# DACN_shematic.net
KiCad netlist of a schematic drawn in Altium Designer
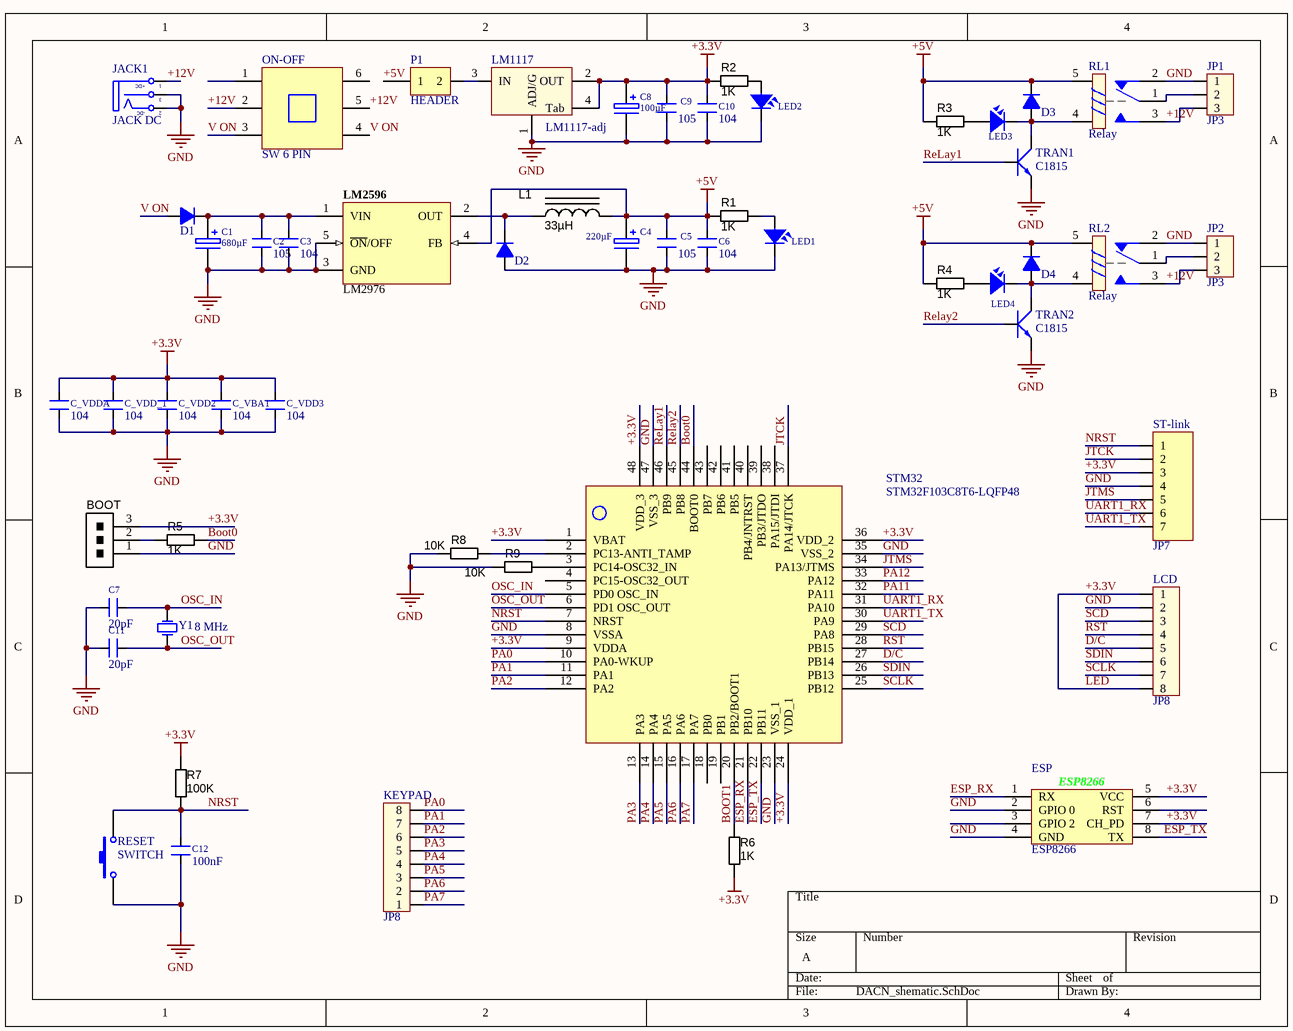
[diagram p0: DACN_shematic.SchDoc]

(export (version "E")
  (design (tool "Eeschema 10.0.6"))
  (components
    (comp (ref "BOOT")
      (value "CONN_HEADER_1x3P_0.100in")
      (footprint "1x3POS_HEADER")
      (description "Pin Header, THT, Single-row, 2.54mm pitch")
      (libsource (lib "My library altium") (part "CONN_HEADER_1x3P_0.100in"))
    )
    (comp (ref "C1")
      (value "10µF")
      (footprint "CAP_ELEC_5x5.7")
      (fields (field (name "ALTIUM_UNNAMED_1") "680µF"))
      (libsource (lib "My library altium") (part "CAP Aluminum"))
    )
    (comp (ref "C2")
      (value "105")
      (footprint "SM-CAP-0805")
      (fields (field (name "DESIGNED BY") "VanDungEvn"))
      (libsource (lib "My library altium") (part "CAP SMD"))
    )
    (comp (ref "C3")
      (value "104")
      (footprint "SM-CAP-0805")
      (fields (field (name "DESIGNED BY") "VanDungEvn"))
      (libsource (lib "My library altium") (part "CAP SMD"))
    )
    (comp (ref "C4")
      (value "10µF")
      (footprint "CAP_ELEC_5x5.7")
      (fields (field (name "ALTIUM_UNNAMED_1") "220µF"))
      (libsource (lib "My library altium") (part "CAP Aluminum"))
    )
    (comp (ref "C5")
      (value "105")
      (footprint "SM-CAP-0805")
      (fields (field (name "DESIGNED BY") "VanDungEvn"))
      (libsource (lib "My library altium") (part "CAP SMD"))
    )
    (comp (ref "C6")
      (value "104")
      (footprint "SM-CAP-0805")
      (fields (field (name "DESIGNED BY") "VanDungEvn"))
      (libsource (lib "My library altium") (part "CAP SMD"))
    )
    (comp (ref "C7")
      (value "20pF")
      (footprint "SM-CAP-0805")
      (fields (field (name "DESIGNED BY") "VanDungEvn"))
      (libsource (lib "My library altium") (part "CAP SMD"))
    )
    (comp (ref "C8")
      (value "10µF")
      (footprint "CAP_ELEC_5x5.7")
      (fields (field (name "ALTIUM_UNNAMED_1") "100µF"))
      (libsource (lib "My library altium") (part "CAP Aluminum"))
    )
    (comp (ref "C9")
      (value "105")
      (footprint "SM-CAP-0805")
      (fields (field (name "DESIGNED BY") "VanDungEvn"))
      (libsource (lib "My library altium") (part "CAP SMD"))
    )
    (comp (ref "C10")
      (value "104")
      (footprint "SM-CAP-0805")
      (fields (field (name "DESIGNED BY") "VanDungEvn"))
      (libsource (lib "My library altium") (part "CAP SMD"))
    )
    (comp (ref "C11")
      (value "20pF")
      (footprint "SM-CAP-0805")
      (fields (field (name "DESIGNED BY") "VanDungEvn"))
      (libsource (lib "My library altium") (part "CAP SMD"))
    )
    (comp (ref "C12")
      (value "100nF")
      (footprint "SM-CAP-0805")
      (fields (field (name "DESIGNED BY") "VanDungEvn"))
      (libsource (lib "My library altium") (part "CAP SMD"))
    )
    (comp (ref "C_VBAT")
      (value "104")
      (footprint "SM-CAP-0805")
      (fields (field (name "DESIGNED BY") "VanDungEvn"))
      (libsource (lib "My library altium") (part "CAP SMD"))
    )
    (comp (ref "C_VDD2")
      (value "104")
      (footprint "SM-CAP-0805")
      (fields (field (name "DESIGNED BY") "VanDungEvn"))
      (libsource (lib "My library altium") (part "CAP SMD"))
    )
    (comp (ref "C_VDD3")
      (value "104")
      (footprint "SM-CAP-0805")
      (fields (field (name "DESIGNED BY") "VanDungEvn"))
      (libsource (lib "My library altium") (part "CAP SMD"))
    )
    (comp (ref "C_VDDA")
      (value "104")
      (footprint "SM-CAP-0805")
      (fields (field (name "DESIGNED BY") "VanDungEvn"))
      (libsource (lib "My library altium") (part "CAP SMD"))
    )
    (comp (ref "C_VDD_1")
      (value "104")
      (footprint "SM-CAP-0805")
      (fields (field (name "DESIGNED BY") "VanDungEvn"))
      (libsource (lib "My library altium") (part "CAP SMD"))
    )
    (comp (ref "D1")
      (value "Diode  1N4007")
      (footprint "DO-214AC")
      (description "Diode 1A")
      (libsource (lib "My library altium") (part "Diode  1N4007"))
    )
    (comp (ref "D2")
      (value "Diode  1N4007")
      (footprint "DO-214AC")
      (description "Diode 1A")
      (libsource (lib "My library altium") (part "Diode  1N4007"))
    )
    (comp (ref "D3")
      (value "Diode  1N4007")
      (footprint "DO-214AC")
      (description "Diode 1A")
      (libsource (lib "My library altium") (part "Diode  1N4007"))
    )
    (comp (ref "D4")
      (value "Diode  1N4007")
      (footprint "DO-214AC")
      (description "Diode 1A")
      (libsource (lib "My library altium") (part "Diode  1N4007"))
    )
    (comp (ref "ESP")
      (value "ESP8266")
      (footprint "ESP2866")
      (libsource (lib "My library altium") (part "ESP8266"))
    )
    (comp (ref "JACK1")
      (value "JACK DC")
      (footprint "JACK DC")
      (libsource (lib "ThinhNguyenLib") (part "JACK DC"))
    )
    (comp (ref "JP1")
      (value "JP3")
      (footprint "CON3")
      (description "Connector 3")
      (libsource (lib "My library altium") (part "Con3"))
    )
    (comp (ref "JP2")
      (value "JP3")
      (footprint "CON3")
      (description "Connector 3")
      (libsource (lib "My library altium") (part "Con3"))
    )
    (comp (ref "KEYPAD")
      (value "JP8")
      (footprint "jam8")
      (description "jam 8")
      (libsource (lib "") (part "jam 8_1"))
    )
    (comp (ref "L1")
      (value "33µH")
      (footprint "IND_WW_DR73")
      (description "Inductor Power 10µH 2.1A 7.6x7.6mm SMD")
      (fields (field (name "TOLERANCE") "±20%"))
      (libsource (lib "My library altium") (part "INDC_10u_DR73-100-R"))
    )
    (comp (ref "LCD")
      (value "JP8")
      (footprint "jam8")
      (description "jam 8")
      (libsource (lib "My library altium") (part "jam 8"))
    )
    (comp (ref "LED1")
      (value "LED SMD")
      (footprint "SM-LED-0805-Blue")
      (libsource (lib "My library altium") (part "LED SMD 0805"))
    )
    (comp (ref "LED2")
      (value "LED SMD")
      (footprint "SM-LED-0805-Blue")
      (libsource (lib "My library altium") (part "LED SMD 0805"))
    )
    (comp (ref "LED3")
      (value "LED SMD")
      (footprint "SM-LED-0805-Blue")
      (libsource (lib "My library altium") (part "LED SMD 0805"))
    )
    (comp (ref "LED4")
      (value "LED SMD")
      (footprint "SM-LED-0805-Blue")
      (libsource (lib "My library altium") (part "LED SMD 0805"))
    )
    (comp (ref "LM1117")
      (value "LM1117-adj")
      (footprint "SOT223-4N")
      (description "3v3")
      (libsource (lib "My library altium") (part "LM1117-adj"))
    )
    (comp (ref "LM2596") (value "LM2976") (footprint "TO263") (libsource (lib "LIBRARY") (part "LM2596")))
    (comp (ref "ON-OFF")
      (value "SW 6 PIN")
      (footprint "SW6")
      (libsource (lib "ThinhNguyenLib") (part "SW 6 PIN"))
    )
    (comp (ref "P1")
      (value "HEADER")
      (footprint "JUMPER PITCH 2 PIN")
      (libsource (lib "ThinhNguyenLib") (part "HEADER CONNECT"))
    )
    (comp (ref "R1")
      (value "1K")
      (footprint "RESC2012N_ZERO")
      (description "Resistor SMD chip 0.0 Ohm 0.125W 0805")
      (fields (field (name "Comment") "Jumper"))
      (libsource (lib "") (part "RES_0805_1"))
    )
    (comp (ref "R2")
      (value "1K")
      (footprint "RESC2012N_ZERO")
      (description "Resistor SMD chip 0.0 Ohm 0.125W 0805")
      (fields (field (name "Comment") "Jumper"))
      (libsource (lib "") (part "RES_0805_1"))
    )
    (comp (ref "R3")
      (value "1K")
      (footprint "RESC2012N_ZERO")
      (description "Resistor SMD chip 0.0 Ohm 0.125W 0805")
      (fields (field (name "Comment") "Jumper"))
      (libsource (lib "") (part "RES_0805_1"))
    )
    (comp (ref "R4")
      (value "1K")
      (footprint "RESC2012N_ZERO")
      (description "Resistor SMD chip 0.0 Ohm 0.125W 0805")
      (fields (field (name "Comment") "Jumper"))
      (libsource (lib "") (part "RES_0805_1"))
    )
    (comp (ref "R5")
      (value "1K")
      (footprint "RESC2012N_ZERO")
      (description "Resistor SMD chip 0.0 Ohm 0.125W 0805")
      (fields (field (name "Comment") "Jumper"))
      (libsource (lib "") (part "RES_0805_1"))
    )
    (comp (ref "R6")
      (value "1K")
      (footprint "RESC2012N_ZERO")
      (description "Resistor SMD chip 0.0 Ohm 0.125W 0805")
      (fields (field (name "Comment") "Jumper"))
      (libsource (lib "") (part "RES_0805_2"))
    )
    (comp (ref "R7")
      (value "100K")
      (footprint "RESC2012N_ZERO")
      (description "Resistor SMD chip 0.0 Ohm 0.125W 0805")
      (fields (field (name "Comment") "Jumper"))
      (libsource (lib "") (part "RES_0805_2"))
    )
    (comp (ref "R8")
      (value "10K")
      (footprint "RESC2012N_ZERO")
      (description "Resistor SMD chip 0.0 Ohm 0.125W 0805")
      (fields (field (name "Comment") "Jumper"))
      (libsource (lib "My library altium") (part "RES_0805"))
    )
    (comp (ref "R9")
      (value "10K")
      (footprint "RESC2012N_ZERO")
      (description "Resistor SMD chip 0.0 Ohm 0.125W 0805")
      (fields (field (name "Comment") "Jumper"))
      (libsource (lib "My library altium") (part "RES_0805"))
    )
    (comp (ref "RESET")
      (value "SWITCH")
      (footprint "SW 4PIN")
      (fields (field (name "PUBLISHER") "Altium Limited"))
      (libsource (lib "ThinhNguyenLib") (part "SWITCH"))
    )
    (comp (ref "RL1")
      (value "Relay")
      (footprint "RL_SPDT_10A")
      (description "Relay SPDT 5 Pin")
      (libsource (lib "My library altium") (part "Relay SRD"))
    )
    (comp (ref "RL2")
      (value "Relay")
      (footprint "RL_SPDT_10A")
      (description "Relay SPDT 5 Pin")
      (libsource (lib "My library altium") (part "Relay SRD"))
    )
    (comp (ref "ST-link")
      (value "JP7")
      (footprint "JP7-D1T")
      (description "WR-PHD 2.54 mm Angled Socket Header")
      (fields
        (field (name "MANUFACTURER") "Würth Elektronik eiSos GmbH")
        (field (name "PARTNO") "613007143121")
        (field (name "CREATED BY") "Karrer Zheng")
      )
      (libsource (lib "LIBRARY") (part "JP7"))
    )
    (comp (ref "STM32")
      (value "STM32F103C8T6-LQFP48")
      (footprint "LQFP 48 PIN")
      (fields (field (name "PUBLISHER") "Altium Limited"))
      (libsource (lib "ThinhNguyenLib") (part "STM32F103C8T6-LQFP48"))
    )
    (comp (ref "TRAN1")
      (value "C1815")
      (footprint "C1815")
      (description "NPN 600mW, ECB")
      (libsource (lib "My library altium") (part "C1815"))
    )
    (comp (ref "TRAN2")
      (value "C1815")
      (footprint "C1815")
      (description "NPN 600mW, ECB")
      (libsource (lib "My library altium") (part "C1815"))
    )
    (comp (ref "Y1")
      (value "8 MHz")
      (footprint "CRYSTAL DIP")
      (fields (field (name "PUBLISHER") "Altium Limited"))
      (libsource (lib "ThinhNguyenLib") (part "Crystal"))
    )
  )
  (nets
    (net (code "1") (name "+3.3V") (class "Default")
      (node (ref "BOOT") (pin "3") (pinfunction "3_3") (pintype "passive"))
      (node (ref "C10") (pin "2") (pinfunction "2_2") (pintype "passive"))
      (node (ref "C8") (pin "1") (pintype "passive"))
      (node (ref "C9") (pin "2") (pinfunction "2_2") (pintype "passive"))
      (node (ref "C_VBAT") (pin "2") (pinfunction "2_2") (pintype "passive"))
      (node (ref "C_VDD2") (pin "2") (pinfunction "2_2") (pintype "passive"))
      (node (ref "C_VDD3") (pin "2") (pinfunction "2_2") (pintype "passive"))
      (node (ref "C_VDDA") (pin "2") (pinfunction "2_2") (pintype "passive"))
      (node (ref "C_VDD_1") (pin "2") (pinfunction "2_2") (pintype "passive"))
      (node (ref "ESP") (pin "5") (pinfunction "VCC_5") (pintype "passive"))
      (node (ref "ESP") (pin "7") (pinfunction "CH_PD_7") (pintype "passive"))
      (node (ref "LCD") (pin "1") (pinfunction "1_1") (pintype "passive"))
      (node (ref "LCD") (pin "8") (pinfunction "8_8") (pintype "passive"))
      (node (ref "LM1117") (pin "2") (pinfunction "OUT_2") (pintype "passive"))
      (node (ref "LM1117") (pin "4") (pinfunction "Tab_4") (pintype "passive"))
      (node (ref "R2") (pin "1") (pinfunction "1_1") (pintype "passive"))
      (node (ref "R6") (pin "1") (pinfunction "1_1") (pintype "passive"))
      (node (ref "R7") (pin "2") (pinfunction "2_2") (pintype "passive"))
      (node (ref "ST-link") (pin "3") (pinfunction "3_3") (pintype "passive"))
      (node (ref "STM32") (pin "1") (pinfunction "VBAT_1") (pintype "passive"))
      (node (ref "STM32") (pin "24") (pinfunction "VDD_1_24") (pintype "passive"))
      (node (ref "STM32") (pin "36") (pinfunction "VDD_2_36") (pintype "passive"))
      (node (ref "STM32") (pin "48") (pinfunction "VDD_3_48") (pintype "passive"))
      (node (ref "STM32") (pin "9") (pinfunction "VDDA_9") (pintype "passive"))
    )
    (net (code "2") (name "+5V") (class "Default")
      (node (ref "C4") (pin "1") (pintype "passive"))
      (node (ref "C5") (pin "2") (pinfunction "2_2") (pintype "passive"))
      (node (ref "C6") (pin "2") (pinfunction "2_2") (pintype "passive"))
      (node (ref "D3") (pin "K") (pinfunction "K_K") (pintype "passive"))
      (node (ref "D4") (pin "K") (pinfunction "K_K") (pintype "passive"))
      (node (ref "L1") (pin "2") (pinfunction "2_2") (pintype "passive"))
      (node (ref "LM2596") (pin "4") (pinfunction "FB_4") (pintype "input"))
      (node (ref "P1") (pin "1") (pinfunction "1_1") (pintype "passive"))
      (node (ref "R1") (pin "1") (pinfunction "1_1") (pintype "passive"))
      (node (ref "R3") (pin "1") (pinfunction "1_1") (pintype "passive"))
      (node (ref "R4") (pin "1") (pinfunction "1_1") (pintype "passive"))
      (node (ref "RL1") (pin "5") (pinfunction "5_5") (pintype "passive"))
      (node (ref "RL2") (pin "5") (pinfunction "5_5") (pintype "passive"))
    )
    (net (code "3") (name "/+12V") (class "Default")
      (node (ref "JACK1") (pin "1") (pinfunction "T_1") (pintype "passive"))
      (node (ref "JP1") (pin "3") (pinfunction "3_3") (pintype "passive"))
      (node (ref "JP2") (pin "3") (pinfunction "3_3") (pintype "passive"))
      (node (ref "ON-OFF") (pin "2") (pinfunction "2_2") (pintype "passive"))
      (node (ref "ON-OFF") (pin "5") (pinfunction "5_5") (pintype "passive"))
      (node (ref "RL1") (pin "3") (pinfunction "3_3") (pintype "passive"))
      (node (ref "RL2") (pin "3") (pinfunction "3_3") (pintype "passive"))
    )
    (net (code "4") (name "/BOOT1") (class "Default")
      (node (ref "R6") (pin "2") (pinfunction "2_2") (pintype "passive"))
      (node (ref "STM32") (pin "20") (pinfunction "PB2/BOOT1_20") (pintype "passive"))
    )
    (net (code "5") (name "/Boot0") (class "Default")
      (node (ref "R5") (pin "2") (pinfunction "2_2") (pintype "passive"))
      (node (ref "STM32") (pin "44") (pinfunction "BOOT0_44") (pintype "passive"))
    )
    (net (code "6") (name "/D{slash}C") (class "Default")
      (node (ref "LCD") (pin "5") (pinfunction "5_5") (pintype "passive"))
      (node (ref "STM32") (pin "27") (pinfunction "PB14_27") (pintype "passive"))
    )
    (net (code "7") (name "/ESP_RX") (class "Default")
      (node (ref "ESP") (pin "1") (pinfunction "RX_1") (pintype "passive"))
      (node (ref "STM32") (pin "21") (pinfunction "PB10_21") (pintype "passive"))
    )
    (net (code "8") (name "/ESP_TX") (class "Default")
      (node (ref "ESP") (pin "8") (pinfunction "TX_8") (pintype "passive"))
      (node (ref "STM32") (pin "22") (pinfunction "PB11_22") (pintype "passive"))
    )
    (net (code "9") (name "/JTCK") (class "Default")
      (node (ref "ST-link") (pin "2") (pinfunction "2_2") (pintype "passive"))
      (node (ref "STM32") (pin "37") (pinfunction "PA14/JTCK_37") (pintype "passive"))
    )
    (net (code "10") (name "/JTMS") (class "Default")
      (node (ref "ST-link") (pin "5") (pinfunction "5_5") (pintype "passive"))
      (node (ref "STM32") (pin "34") (pinfunction "PA13/JTMS_34") (pintype "passive"))
    )
    (net (code "11") (name "/NRST") (class "Default")
      (node (ref "C12") (pin "1") (pinfunction "1_1") (pintype "passive"))
      (node (ref "R7") (pin "1") (pinfunction "1_1") (pintype "passive"))
      (node (ref "RESET") (pin "2") (pinfunction "2_2") (pintype "passive"))
      (node (ref "ST-link") (pin "1") (pinfunction "1_1") (pintype "passive"))
      (node (ref "STM32") (pin "7") (pinfunction "NRST_7") (pintype "passive"))
    )
    (net (code "12") (name "/OSC_IN") (class "Default")
      (node (ref "C7") (pin "1") (pinfunction "1_1") (pintype "passive"))
      (node (ref "STM32") (pin "5") (pinfunction "PD0_OSC_IN_5") (pintype "passive"))
      (node (ref "Y1") (pin "2") (pinfunction "OSC2_2") (pintype "passive"))
    )
    (net (code "13") (name "/OSC_OUT") (class "Default")
      (node (ref "C11") (pin "1") (pinfunction "1_1") (pintype "passive"))
      (node (ref "STM32") (pin "6") (pinfunction "PD1_OSC_OUT_6") (pintype "passive"))
      (node (ref "Y1") (pin "1") (pinfunction "OSC1_1") (pintype "passive"))
    )
    (net (code "14") (name "/PA0") (class "Default")
      (node (ref "KEYPAD") (pin "8") (pinfunction "8_8") (pintype "passive"))
      (node (ref "STM32") (pin "10") (pinfunction "PA0-WKUP_10") (pintype "passive"))
    )
    (net (code "15") (name "/PA1") (class "Default")
      (node (ref "KEYPAD") (pin "7") (pinfunction "7_7") (pintype "passive"))
      (node (ref "STM32") (pin "11") (pinfunction "PA1_11") (pintype "passive"))
    )
    (net (code "16") (name "/PA2") (class "Default")
      (node (ref "KEYPAD") (pin "6") (pinfunction "6_6") (pintype "passive"))
      (node (ref "STM32") (pin "12") (pinfunction "PA2_12") (pintype "passive"))
    )
    (net (code "17") (name "/PA3") (class "Default")
      (node (ref "KEYPAD") (pin "5") (pinfunction "5_5") (pintype "passive"))
      (node (ref "STM32") (pin "13") (pinfunction "PA3_13") (pintype "passive"))
    )
    (net (code "18") (name "/PA4") (class "Default")
      (node (ref "KEYPAD") (pin "4") (pinfunction "4_4") (pintype "passive"))
      (node (ref "STM32") (pin "14") (pinfunction "PA4_14") (pintype "passive"))
    )
    (net (code "19") (name "/PA5") (class "Default")
      (node (ref "KEYPAD") (pin "3") (pinfunction "3_3") (pintype "passive"))
      (node (ref "STM32") (pin "15") (pinfunction "PA5_15") (pintype "passive"))
    )
    (net (code "20") (name "/PA6") (class "Default")
      (node (ref "KEYPAD") (pin "2") (pinfunction "2_2") (pintype "passive"))
      (node (ref "STM32") (pin "16") (pinfunction "PA6_16") (pintype "passive"))
    )
    (net (code "21") (name "/PA7") (class "Default")
      (node (ref "KEYPAD") (pin "1") (pinfunction "1_1") (pintype "passive"))
      (node (ref "STM32") (pin "17") (pinfunction "PA7_17") (pintype "passive"))
    )
    (net (code "22") (name "/PA11") (class "Default")
      (node (ref "STM32") (pin "32") (pinfunction "PA11_32") (pintype "passive"))
    )
    (net (code "23") (name "/PA12") (class "Default")
      (node (ref "STM32") (pin "33") (pinfunction "PA12_33") (pintype "passive"))
    )
    (net (code "24") (name "/RST") (class "Default")
      (node (ref "LCD") (pin "4") (pinfunction "4_4") (pintype "passive"))
      (node (ref "STM32") (pin "28") (pinfunction "PB15_28") (pintype "passive"))
    )
    (net (code "25") (name "/ReLay1") (class "Default")
      (node (ref "STM32") (pin "46") (pinfunction "PB9_46") (pintype "passive"))
      (node (ref "TRAN1") (pin "1") (pinfunction "B_1") (pintype "passive"))
    )
    (net (code "26") (name "/Relay2") (class "Default")
      (node (ref "STM32") (pin "45") (pinfunction "PB8_45") (pintype "passive"))
      (node (ref "TRAN2") (pin "1") (pinfunction "B_1") (pintype "passive"))
    )
    (net (code "27") (name "/SCD") (class "Default")
      (node (ref "LCD") (pin "3") (pinfunction "3_3") (pintype "passive"))
      (node (ref "STM32") (pin "29") (pinfunction "PA8_29") (pintype "passive"))
    )
    (net (code "28") (name "/SCLK") (class "Default")
      (node (ref "LCD") (pin "7") (pinfunction "7_7") (pintype "passive"))
      (node (ref "STM32") (pin "25") (pinfunction "PB12_25") (pintype "passive"))
    )
    (net (code "29") (name "/SDIN") (class "Default")
      (node (ref "LCD") (pin "6") (pinfunction "6_6") (pintype "passive"))
      (node (ref "STM32") (pin "26") (pinfunction "PB13_26") (pintype "passive"))
    )
    (net (code "30") (name "/UART1_RX") (class "Default")
      (node (ref "ST-link") (pin "6") (pinfunction "6_6") (pintype "passive"))
      (node (ref "STM32") (pin "31") (pinfunction "PA10_31") (pintype "passive"))
    )
    (net (code "31") (name "/UART1_TX") (class "Default")
      (node (ref "ST-link") (pin "7") (pinfunction "7_7") (pintype "passive"))
      (node (ref "STM32") (pin "30") (pinfunction "PA9_30") (pintype "passive"))
    )
    (net (code "32") (name "/V ON") (class "Default")
      (node (ref "D1") (pin "A") (pinfunction "A_A") (pintype "passive"))
      (node (ref "ON-OFF") (pin "3") (pinfunction "3_3") (pintype "passive"))
      (node (ref "ON-OFF") (pin "4") (pinfunction "4_4") (pintype "passive"))
    )
    (net (code "33") (name "GND") (class "Default")
      (node (ref "BOOT") (pin "1") (pinfunction "1_1") (pintype "passive"))
      (node (ref "C1") (pin "2") (pintype "passive"))
      (node (ref "C10") (pin "1") (pinfunction "1_1") (pintype "passive"))
      (node (ref "C11") (pin "2") (pinfunction "2_2") (pintype "passive"))
      (node (ref "C12") (pin "2") (pinfunction "2_2") (pintype "passive"))
      (node (ref "C2") (pin "1") (pinfunction "1_1") (pintype "passive"))
      (node (ref "C3") (pin "1") (pinfunction "1_1") (pintype "passive"))
      (node (ref "C4") (pin "2") (pintype "passive"))
      (node (ref "C5") (pin "1") (pinfunction "1_1") (pintype "passive"))
      (node (ref "C6") (pin "1") (pinfunction "1_1") (pintype "passive"))
      (node (ref "C7") (pin "2") (pinfunction "2_2") (pintype "passive"))
      (node (ref "C8") (pin "2") (pintype "passive"))
      (node (ref "C9") (pin "1") (pinfunction "1_1") (pintype "passive"))
      (node (ref "C_VBAT") (pin "1") (pinfunction "1_1") (pintype "passive"))
      (node (ref "C_VDD2") (pin "1") (pinfunction "1_1") (pintype "passive"))
      (node (ref "C_VDD3") (pin "1") (pinfunction "1_1") (pintype "passive"))
      (node (ref "C_VDDA") (pin "1") (pinfunction "1_1") (pintype "passive"))
      (node (ref "C_VDD_1") (pin "1") (pinfunction "1_1") (pintype "passive"))
      (node (ref "D2") (pin "A") (pinfunction "A_A") (pintype "passive"))
      (node (ref "ESP") (pin "2") (pinfunction "GPIO_0_2") (pintype "passive"))
      (node (ref "ESP") (pin "4") (pinfunction "GND_4") (pintype "passive"))
      (node (ref "JACK1") (pin "2") (pinfunction "TN_2") (pintype "passive"))
      (node (ref "JACK1") (pin "3") (pinfunction "S_3") (pintype "power_in"))
      (node (ref "JP1") (pin "1") (pinfunction "1_1") (pintype "passive"))
      (node (ref "JP2") (pin "1") (pinfunction "1_1") (pintype "passive"))
      (node (ref "LCD") (pin "2") (pinfunction "2_2") (pintype "passive"))
      (node (ref "LED1") (pin "2") (pinfunction "2_2") (pintype "passive"))
      (node (ref "LED2") (pin "2") (pinfunction "2_2") (pintype "passive"))
      (node (ref "LM1117") (pin "1") (pinfunction "ADJ/G_1") (pintype "passive"))
      (node (ref "LM2596") (pin "3") (pinfunction "GND_3") (pintype "power_in"))
      (node (ref "LM2596") (pin "5") (pinfunction "~{ON}/OFF_5") (pintype "input"))
      (node (ref "R8") (pin "2") (pinfunction "2_2") (pintype "passive"))
      (node (ref "R9") (pin "2") (pinfunction "2_2") (pintype "passive"))
      (node (ref "RESET") (pin "1") (pinfunction "1_1") (pintype "passive"))
      (node (ref "RL1") (pin "2") (pinfunction "2_2") (pintype "passive"))
      (node (ref "RL2") (pin "2") (pinfunction "2_2") (pintype "passive"))
      (node (ref "ST-link") (pin "4") (pinfunction "4_4") (pintype "passive"))
      (node (ref "STM32") (pin "23") (pinfunction "VSS_1_23") (pintype "passive"))
      (node (ref "STM32") (pin "35") (pinfunction "VSS_2_35") (pintype "passive"))
      (node (ref "STM32") (pin "47") (pinfunction "VSS_3_47") (pintype "passive"))
      (node (ref "STM32") (pin "8") (pinfunction "VSSA_8") (pintype "passive"))
      (node (ref "TRAN1") (pin "2") (pinfunction "E_2") (pintype "passive"))
      (node (ref "TRAN2") (pin "2") (pinfunction "E_2") (pintype "passive"))
    )
    (net (code "34") (name "Net-(BOOT-Pad2)") (class "Default")
      (node (ref "BOOT") (pin "2") (pinfunction "2_2") (pintype "passive"))
      (node (ref "R5") (pin "1") (pinfunction "1_1") (pintype "passive"))
    )
    (net (code "35") (name "Net-(JP1-Pad2)") (class "Default")
      (node (ref "JP1") (pin "2") (pinfunction "2_2") (pintype "passive"))
      (node (ref "RL1") (pin "1") (pinfunction "1_1") (pintype "passive"))
    )
    (net (code "36") (name "Net-(JP2-Pad2)") (class "Default")
      (node (ref "JP2") (pin "2") (pinfunction "2_2") (pintype "passive"))
      (node (ref "RL2") (pin "1") (pinfunction "1_1") (pintype "passive"))
    )
    (net (code "37") (name "Net-(LED1-Pad1)") (class "Default")
      (node (ref "LED1") (pin "1") (pinfunction "1_1") (pintype "passive"))
      (node (ref "R1") (pin "2") (pinfunction "2_2") (pintype "passive"))
    )
    (net (code "38") (name "Net-(LED2-Pad1)") (class "Default")
      (node (ref "LED2") (pin "1") (pinfunction "1_1") (pintype "passive"))
      (node (ref "R2") (pin "2") (pinfunction "2_2") (pintype "passive"))
    )
    (net (code "39") (name "Net-(LED3-Pad1)") (class "Default")
      (node (ref "LED3") (pin "1") (pinfunction "1_1") (pintype "passive"))
      (node (ref "R3") (pin "2") (pinfunction "2_2") (pintype "passive"))
    )
    (net (code "40") (name "Net-(LED4-Pad1)") (class "Default")
      (node (ref "LED4") (pin "1") (pinfunction "1_1") (pintype "passive"))
      (node (ref "R4") (pin "2") (pinfunction "2_2") (pintype "passive"))
    )
    (net (code "41") (name "Net-(LM1117-IN)") (class "Default")
      (node (ref "LM1117") (pin "3") (pinfunction "IN_3") (pintype "passive"))
      (node (ref "P1") (pin "2") (pinfunction "2_2") (pintype "passive"))
    )
    (net (code "42") (name "Net-(LM2596-OUT)") (class "Default")
      (node (ref "D2") (pin "K") (pinfunction "K_K") (pintype "passive"))
      (node (ref "L1") (pin "1") (pinfunction "1_1") (pintype "passive"))
      (node (ref "LM2596") (pin "2") (pinfunction "OUT_2") (pintype "power_in"))
    )
    (net (code "43") (name "Net-(LM2596-VIN)") (class "Default")
      (node (ref "C1") (pin "1") (pintype "passive"))
      (node (ref "C2") (pin "2") (pinfunction "2_2") (pintype "passive"))
      (node (ref "C3") (pin "2") (pinfunction "2_2") (pintype "passive"))
      (node (ref "D1") (pin "K") (pinfunction "K_K") (pintype "passive"))
      (node (ref "LM2596") (pin "1") (pinfunction "VIN_1") (pintype "power_in"))
    )
    (net (code "44") (name "Net-(STM32-PC13-ANTI_TAMP)") (class "Default")
      (node (ref "R8") (pin "1") (pinfunction "1_1") (pintype "passive"))
      (node (ref "STM32") (pin "2") (pinfunction "PC13-ANTI_TAMP_2") (pintype "passive"))
    )
    (net (code "45") (name "Net-(STM32-PC14-OSC32_IN)") (class "Default")
      (node (ref "R9") (pin "1") (pinfunction "1_1") (pintype "passive"))
      (node (ref "STM32") (pin "3") (pinfunction "PC14-OSC32_IN_3") (pintype "passive"))
    )
    (net (code "46") (name "Net-(TRAN1-C)") (class "Default")
      (node (ref "D3") (pin "A") (pinfunction "A_A") (pintype "passive"))
      (node (ref "LED3") (pin "2") (pinfunction "2_2") (pintype "passive"))
      (node (ref "RL1") (pin "4") (pinfunction "4_4") (pintype "passive"))
      (node (ref "TRAN1") (pin "3") (pinfunction "C_3") (pintype "passive"))
    )
    (net (code "47") (name "Net-(TRAN2-C)") (class "Default")
      (node (ref "D4") (pin "A") (pinfunction "A_A") (pintype "passive"))
      (node (ref "LED4") (pin "2") (pinfunction "2_2") (pintype "passive"))
      (node (ref "RL2") (pin "4") (pinfunction "4_4") (pintype "passive"))
      (node (ref "TRAN2") (pin "3") (pinfunction "C_3") (pintype "passive"))
    )
    (net (code "48") (name "unconnected-(ESP-GPIO_2-Pad3)") (class "Default")
      (node (ref "ESP") (pin "3") (pinfunction "GPIO_2_3") (pintype "passive"))
    )
    (net (code "49") (name "unconnected-(ESP-RST-Pad6)") (class "Default")
      (node (ref "ESP") (pin "6") (pinfunction "RST_6") (pintype "passive"))
    )
    (net (code "50") (name "unconnected-(ON-OFF-Pad1)") (class "Default")
      (node (ref "ON-OFF") (pin "1") (pinfunction "1_1") (pintype "passive"))
    )
    (net (code "51") (name "unconnected-(ON-OFF-Pad6)") (class "Default")
      (node (ref "ON-OFF") (pin "6") (pinfunction "6_6") (pintype "passive"))
    )
    (net (code "52") (name "unconnected-(STM32-PA15{slash}JTDI-Pad38)") (class "Default")
      (node (ref "STM32") (pin "38") (pinfunction "PA15/JTDI_38") (pintype "passive"))
    )
    (net (code "53") (name "unconnected-(STM32-PB0-Pad18)") (class "Default")
      (node (ref "STM32") (pin "18") (pinfunction "PB0_18") (pintype "passive"))
    )
    (net (code "54") (name "unconnected-(STM32-PB1-Pad19)") (class "Default")
      (node (ref "STM32") (pin "19") (pinfunction "PB1_19") (pintype "passive"))
    )
    (net (code "55") (name "unconnected-(STM32-PB3{slash}JTDO-Pad39)") (class "Default")
      (node (ref "STM32") (pin "39") (pinfunction "PB3/JTDO_39") (pintype "passive"))
    )
    (net (code "56") (name "unconnected-(STM32-PB4{slash}JNTRST-Pad40)") (class "Default")
      (node (ref "STM32") (pin "40") (pinfunction "PB4/JNTRST_40") (pintype "passive"))
    )
    (net (code "57") (name "unconnected-(STM32-PB5-Pad41)") (class "Default")
      (node (ref "STM32") (pin "41") (pinfunction "PB5_41") (pintype "passive"))
    )
    (net (code "58") (name "unconnected-(STM32-PB6-Pad42)") (class "Default")
      (node (ref "STM32") (pin "42") (pinfunction "PB6_42") (pintype "passive"))
    )
    (net (code "59") (name "unconnected-(STM32-PB7-Pad43)") (class "Default")
      (node (ref "STM32") (pin "43") (pinfunction "PB7_43") (pintype "passive"))
    )
    (net (code "60") (name "unconnected-(STM32-PC15-OSC32_OUT-Pad4)") (class "Default")
      (node (ref "STM32") (pin "4") (pinfunction "PC15-OSC32_OUT_4") (pintype "passive"))
    )
  )
)
